# LTC4063-TestBoard.net
KiCad netlist of a schematic drawn in EAGLE
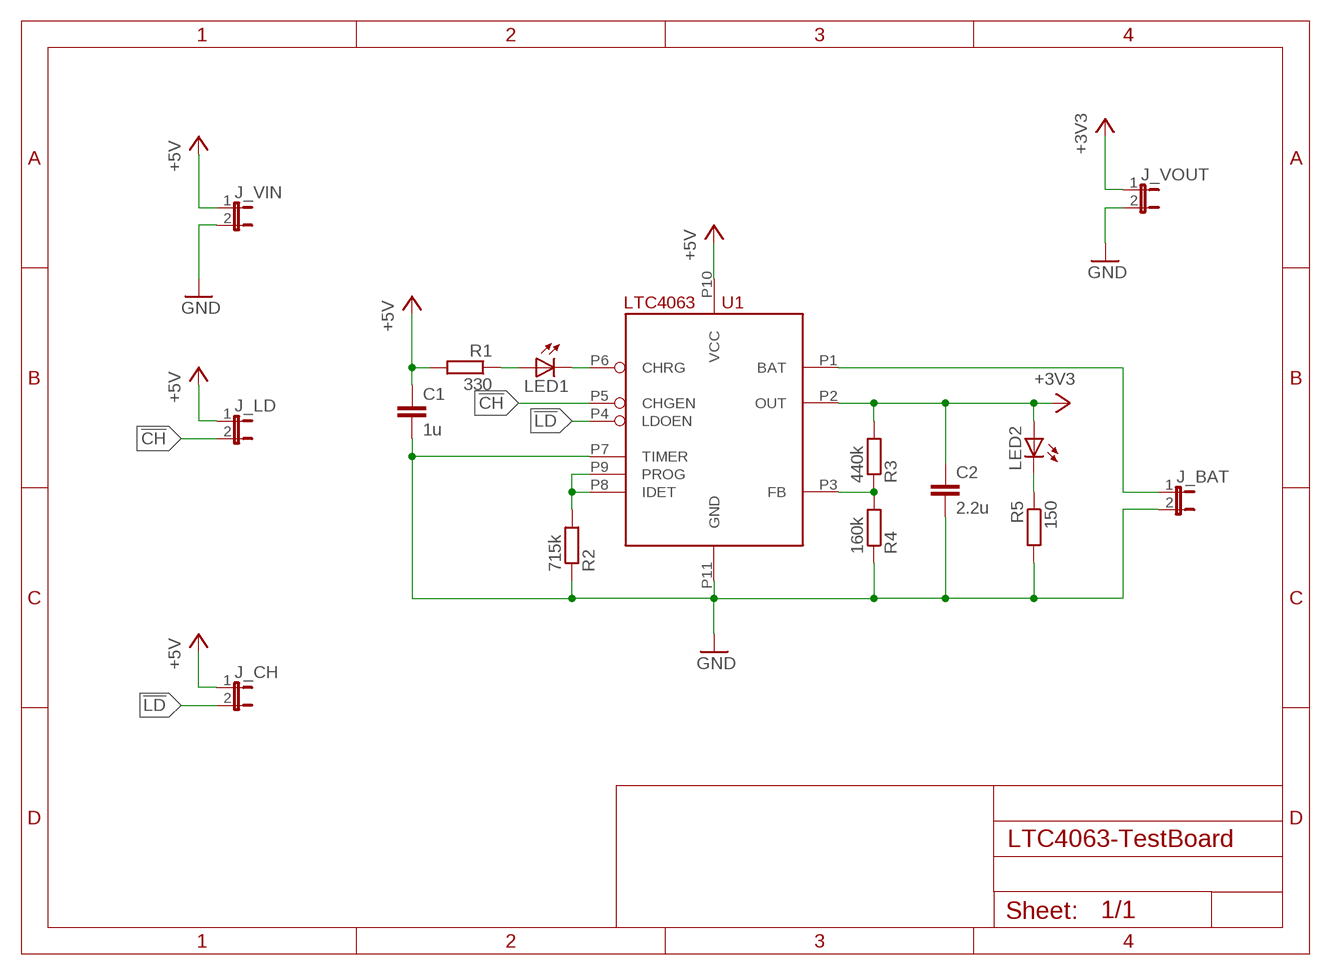
[diagram p0: schematic, sheet 1]

(export (version "E")
  (design (tool "Eeschema 10.0.6"))
  (components
    (comp (ref "C1")
      (value "1u")
      (footprint "eagle-import:C0805K")
      (libsource (lib "eagle-import") (part "C-EUC0805K"))
    )
    (comp (ref "C2")
      (value "2.2u")
      (footprint "eagle-import:C0805K")
      (libsource (lib "eagle-import") (part "C-EUC0805K"))
    )
    (comp (ref "J_BAT")
      (value "JP1E")
      (footprint "eagle-import:JP1")
      (libsource (lib "eagle-import") (part "JP1E"))
    )
    (comp (ref "J_CH")
      (value "JP1E")
      (footprint "eagle-import:JP1")
      (libsource (lib "eagle-import") (part "JP1E"))
    )
    (comp (ref "J_LD")
      (value "JP1E")
      (footprint "eagle-import:JP1")
      (libsource (lib "eagle-import") (part "JP1E"))
    )
    (comp (ref "J_VIN")
      (value "JP1E")
      (footprint "eagle-import:JP1")
      (libsource (lib "eagle-import") (part "JP1E"))
    )
    (comp (ref "J_VOUT")
      (value "JP1E")
      (footprint "eagle-import:JP1")
      (libsource (lib "eagle-import") (part "JP1E"))
    )
    (comp (ref "LED1")
      (value "LED3MM")
      (footprint "eagle-import:LED3MM")
      (libsource (lib "eagle-import") (part "LED3MM"))
    )
    (comp (ref "LED2")
      (value "LED3MM")
      (footprint "eagle-import:LED3MM")
      (libsource (lib "eagle-import") (part "LED3MM"))
    )
    (comp (ref "R1")
      (value "330")
      (footprint "eagle-import:R0805")
      (libsource (lib "eagle-import") (part "R-EU_R0805"))
    )
    (comp (ref "R2")
      (value "715k")
      (footprint "eagle-import:R0805")
      (libsource (lib "eagle-import") (part "R-EU_R0805"))
    )
    (comp (ref "R3")
      (value "440k")
      (footprint "eagle-import:R0805")
      (libsource (lib "eagle-import") (part "R-EU_R0805"))
    )
    (comp (ref "R4")
      (value "160k")
      (footprint "eagle-import:R0805")
      (libsource (lib "eagle-import") (part "R-EU_R0805"))
    )
    (comp (ref "R5")
      (value "150")
      (footprint "eagle-import:R0805")
      (libsource (lib "eagle-import") (part "R-EU_R0805"))
    )
    (comp (ref "U1")
      (value "LTC4063")
      (footprint "eagle-import:LTC4063")
      (libsource (lib "eagle-import") (part "LTC4063"))
    )
  )
  (nets
    (net (code "1") (name "+3V3") (class "Default")
      (node (ref "C2") (pin "1") (pinfunction "1_1") (pintype "passive"))
      (node (ref "J_VOUT") (pin "1") (pinfunction "1_1") (pintype "passive"))
      (node (ref "LED2") (pin "A") (pinfunction "A_A") (pintype "passive"))
      (node (ref "R3") (pin "2") (pinfunction "2_2") (pintype "passive"))
      (node (ref "U1") (pin "P2") (pinfunction "OUT_P2") (pintype "output"))
    )
    (net (code "2") (name "+5V") (class "Default")
      (node (ref "C1") (pin "1") (pinfunction "1_1") (pintype "passive"))
      (node (ref "J_CH") (pin "1") (pinfunction "1_1") (pintype "passive"))
      (node (ref "J_LD") (pin "1") (pinfunction "1_1") (pintype "passive"))
      (node (ref "J_VIN") (pin "1") (pinfunction "1_1") (pintype "passive"))
      (node (ref "R1") (pin "2") (pinfunction "2_2") (pintype "passive"))
      (node (ref "U1") (pin "P10") (pinfunction "VCC_P10") (pintype "power_in"))
    )
    (net (code "3") (name "/~{CH}") (class "Default")
      (node (ref "J_LD") (pin "2") (pinfunction "2_2") (pintype "passive"))
      (node (ref "U1") (pin "P5") (pinfunction "CHGEN_P5") (pintype "input"))
    )
    (net (code "4") (name "/~{LD}") (class "Default")
      (node (ref "J_CH") (pin "2") (pinfunction "2_2") (pintype "passive"))
      (node (ref "U1") (pin "P4") (pinfunction "LDOEN_P4") (pintype "input"))
    )
    (net (code "5") (name "GND") (class "Default")
      (node (ref "C1") (pin "2") (pinfunction "2_2") (pintype "passive"))
      (node (ref "C2") (pin "2") (pinfunction "2_2") (pintype "passive"))
      (node (ref "J_BAT") (pin "2") (pinfunction "2_2") (pintype "passive"))
      (node (ref "J_VIN") (pin "2") (pinfunction "2_2") (pintype "passive"))
      (node (ref "J_VOUT") (pin "2") (pinfunction "2_2") (pintype "passive"))
      (node (ref "R2") (pin "1") (pinfunction "1_1") (pintype "passive"))
      (node (ref "R4") (pin "1") (pinfunction "1_1") (pintype "passive"))
      (node (ref "R5") (pin "2") (pinfunction "2_2") (pintype "passive"))
      (node (ref "U1") (pin "P11") (pinfunction "GND_P11") (pintype "power_in"))
      (node (ref "U1") (pin "P7") (pinfunction "TIMER_P7") (pintype "passive"))
    )
    (net (code "6") (name "Net-(LED1-C)") (class "Default")
      (node (ref "LED1") (pin "K") (pinfunction "C_K") (pintype "passive"))
      (node (ref "U1") (pin "P6") (pinfunction "CHRG_P6") (pintype "output"))
    )
    (net (code "7") (name "Net-(LED1-PadA)") (class "Default")
      (node (ref "LED1") (pin "A") (pinfunction "A_A") (pintype "passive"))
      (node (ref "R1") (pin "1") (pinfunction "1_1") (pintype "passive"))
    )
    (net (code "8") (name "Net-(LED2-C)") (class "Default")
      (node (ref "LED2") (pin "K") (pinfunction "C_K") (pintype "passive"))
      (node (ref "R5") (pin "1") (pinfunction "1_1") (pintype "passive"))
    )
    (net (code "9") (name "Net-(U1-BAT)") (class "Default")
      (node (ref "J_BAT") (pin "1") (pinfunction "1_1") (pintype "passive"))
      (node (ref "U1") (pin "P1") (pinfunction "BAT_P1") (pintype "output"))
    )
    (net (code "10") (name "Net-(U1-FB)") (class "Default")
      (node (ref "R3") (pin "1") (pinfunction "1_1") (pintype "passive"))
      (node (ref "R4") (pin "2") (pinfunction "2_2") (pintype "passive"))
      (node (ref "U1") (pin "P3") (pinfunction "FB_P3") (pintype "passive"))
    )
    (net (code "11") (name "Net-(U1-IDET)") (class "Default")
      (node (ref "R2") (pin "2") (pinfunction "2_2") (pintype "passive"))
      (node (ref "U1") (pin "P8") (pinfunction "IDET_P8") (pintype "passive"))
      (node (ref "U1") (pin "P9") (pinfunction "PROG_P9") (pintype "passive"))
    )
  )
)
